# simple-loop-screwsfixed.net
KiCad netlist of a schematic drawn in EAGLE
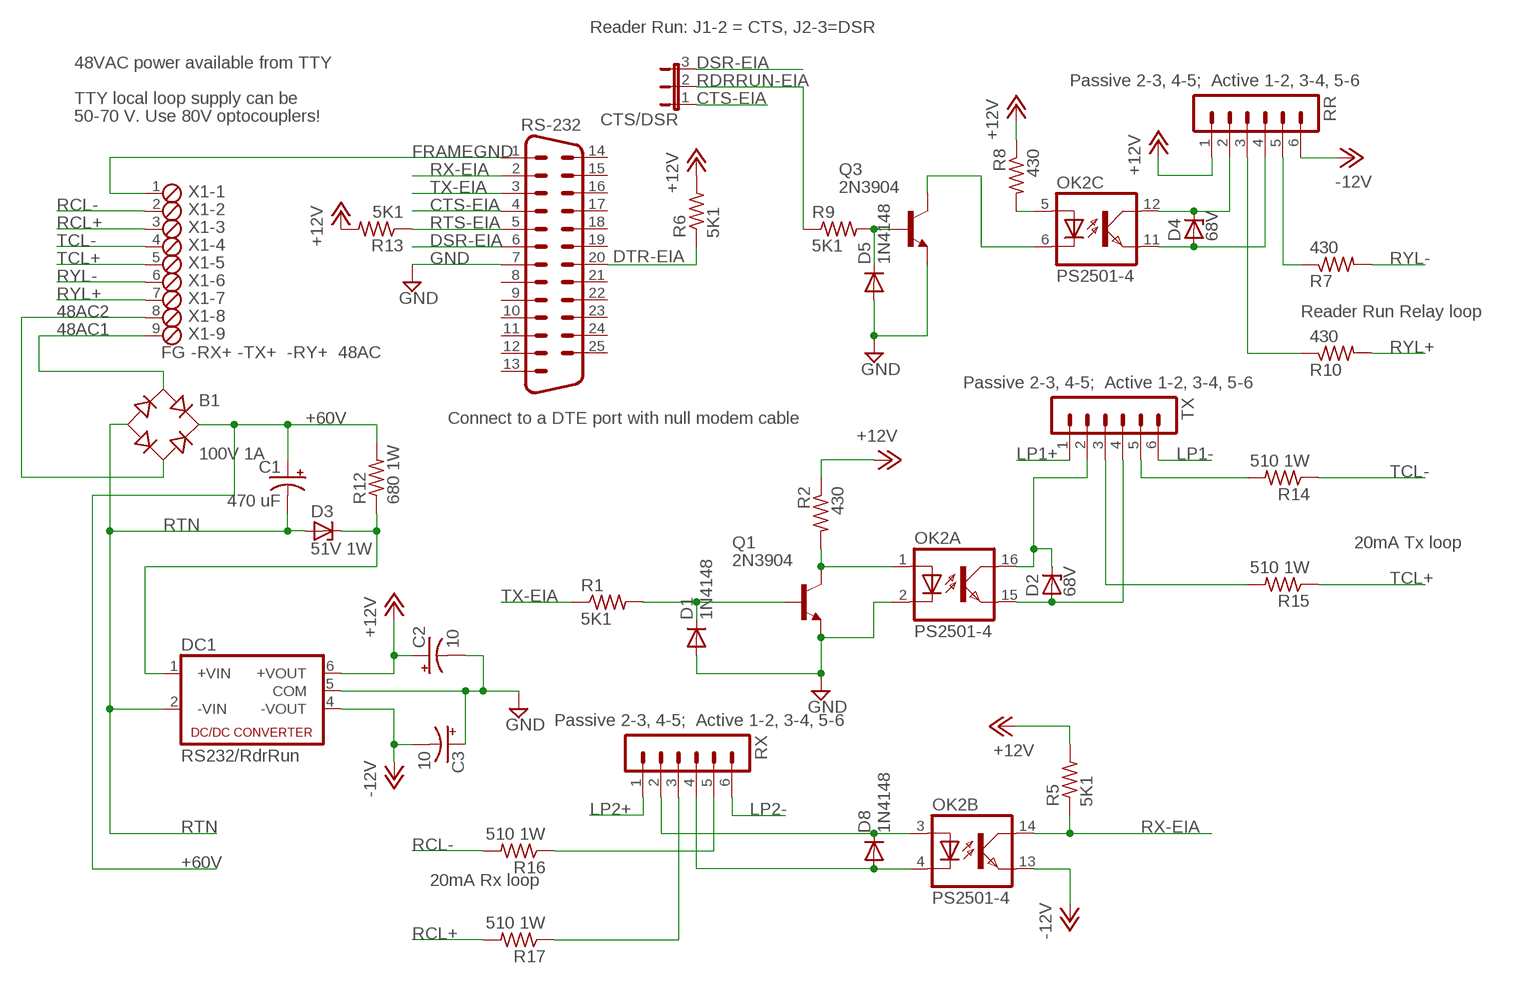
[diagram p0: schematic, sheet 1]
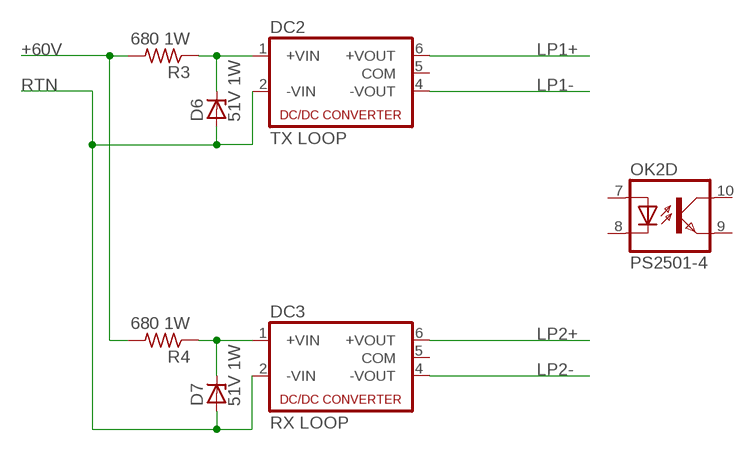
[diagram p1: schematic, sheet 2]

(export (version "E")
  (design (tool "Eeschema 10.0.6"))
  (components
    (comp (ref "B1")
      (value "100V 1A")
      (footprint "eagle-import:RB1A")
      (libsource (lib "eagle-import") (part "RB1A"))
    )
    (comp (ref "C1")
      (value "470 uF")
      (footprint "eagle-import:E7,5-18")
      (libsource (lib "eagle-import") (part "CPOL-USE7.5-18"))
    )
    (comp (ref "C2")
      (value "10")
      (footprint "eagle-import:B45181A")
      (libsource (lib "eagle-import") (part "CPOL-USB45181A"))
    )
    (comp (ref "C3")
      (value "10")
      (footprint "eagle-import:B45181A")
      (libsource (lib "eagle-import") (part "CPOL-USB45181A"))
    )
    (comp (ref "CTS/DSR")
      (value "JP2E")
      (footprint "eagle-import:JP2")
      (libsource (lib "eagle-import") (part "JP2E"))
    )
    (comp (ref "D1")
      (value "1N4148")
      (footprint "eagle-import:DO35-10")
      (libsource (lib "eagle-import") (part "1N4148DO35-10"))
    )
    (comp (ref "D2")
      (value "68V")
      (footprint "eagle-import:DO41Z10")
      (libsource (lib "eagle-import") (part "ZENER-DIODEDO41Z10"))
    )
    (comp (ref "D3")
      (value "51V 1W")
      (footprint "eagle-import:DO41Z10")
      (libsource (lib "eagle-import") (part "ZENER-DIODEDO41Z10"))
    )
    (comp (ref "D4")
      (value "68V")
      (footprint "eagle-import:DO41Z10")
      (libsource (lib "eagle-import") (part "ZENER-DIODEDO41Z10"))
    )
    (comp (ref "D5")
      (value "1N4148")
      (footprint "eagle-import:DO35-10")
      (libsource (lib "eagle-import") (part "1N4148DO35-10"))
    )
    (comp (ref "D8")
      (value "1N4148")
      (footprint "eagle-import:DO35-10")
      (libsource (lib "eagle-import") (part "1N4148DO35-10"))
    )
    (comp (ref "DC1")
      (value "RS232/RdrRun")
      (footprint "eagle-import:NMA")
      (fields (field (name "MF") "C & D TECHNOLOGIES, INC") (field (name "MPN") "NMA0515SC"))
      (libsource (lib "eagle-import") (part "NMA"))
    )
    (comp (ref "OK2")
      (value "PS2501-4")
      (footprint "eagle-import:DIL16")
      (libsource (lib "eagle-import") (part "PC847"))
    )
    (comp (ref "Q1")
      (value "2N3904")
      (footprint "eagle-import:TO92")
      (libsource (lib "eagle-import") (part "2N3904"))
    )
    (comp (ref "Q3")
      (value "2N3904")
      (footprint "eagle-import:TO92")
      (libsource (lib "eagle-import") (part "2N3904"))
    )
    (comp (ref "R1")
      (value "5K1")
      (footprint "eagle-import:0207_10")
      (libsource (lib "eagle-import") (part "R-US_0207/10"))
    )
    (comp (ref "R2")
      (value "430")
      (footprint "eagle-import:0207_10")
      (libsource (lib "eagle-import") (part "R-US_0207/10"))
    )
    (comp (ref "R5")
      (value "5K1")
      (footprint "eagle-import:0207_10")
      (libsource (lib "eagle-import") (part "R-US_0207/10"))
    )
    (comp (ref "R6")
      (value "5K1")
      (footprint "eagle-import:0207_10")
      (libsource (lib "eagle-import") (part "R-US_0207/10"))
    )
    (comp (ref "R7")
      (value "430")
      (footprint "eagle-import:0207_10")
      (libsource (lib "eagle-import") (part "R-US_0207/10"))
    )
    (comp (ref "R8")
      (value "430")
      (footprint "eagle-import:0207_10")
      (libsource (lib "eagle-import") (part "R-US_0207/10"))
    )
    (comp (ref "R9")
      (value "5K1")
      (footprint "eagle-import:0207_10")
      (libsource (lib "eagle-import") (part "R-US_0207/10"))
    )
    (comp (ref "R10")
      (value "430")
      (footprint "eagle-import:0207_10")
      (libsource (lib "eagle-import") (part "R-US_0207/10"))
    )
    (comp (ref "R12")
      (value "680 1W")
      (footprint "eagle-import:P0817V")
      (libsource (lib "eagle-import") (part "R-US_0817/7V"))
    )
    (comp (ref "R13")
      (value "5K1")
      (footprint "eagle-import:0207_10")
      (libsource (lib "eagle-import") (part "R-US_0207/10"))
    )
    (comp (ref "R14")
      (value "510 1W")
      (footprint "eagle-import:P0817V")
      (libsource (lib "eagle-import") (part "R-US_0817/7V"))
    )
    (comp (ref "R15")
      (value "510 1W")
      (footprint "eagle-import:P0817V")
      (libsource (lib "eagle-import") (part "R-US_0817/7V"))
    )
    (comp (ref "R16")
      (value "510 1W")
      (footprint "eagle-import:P0817V")
      (libsource (lib "eagle-import") (part "R-US_0817/7V"))
    )
    (comp (ref "R17")
      (value "510 1W")
      (footprint "eagle-import:P0817V")
      (libsource (lib "eagle-import") (part "R-US_0817/7V"))
    )
    (comp (ref "RR")
      (value "MA06-1")
      (footprint "eagle-import:MA06-1")
      (libsource (lib "eagle-import") (part "MA06-1"))
    )
    (comp (ref "RS-232")
      (value "M25H")
      (footprint "eagle-import:M25H")
      (libsource (lib "eagle-import") (part "M25H"))
    )
    (comp (ref "RX")
      (value "MA06-1")
      (footprint "eagle-import:MA06-1")
      (libsource (lib "eagle-import") (part "MA06-1"))
    )
    (comp (ref "TX")
      (value "MA06-1")
      (footprint "eagle-import:MA06-1")
      (libsource (lib "eagle-import") (part "MA06-1"))
    )
    (comp (ref "X1")
      (value "FG -RX+ -TX+ -RY+ 48AC")
      (footprint "eagle-import:9POL254")
      (libsource (lib "eagle-import") (part "MPT9"))
    )
    (comp (ref "D6")
      (value "51V 1W")
      (footprint "eagle-import:DO41Z10")
      (libsource (lib "eagle-import") (part "ZENER-DIODEDO41Z10"))
    )
    (comp (ref "D7")
      (value "51V 1W")
      (footprint "eagle-import:DO41Z10")
      (libsource (lib "eagle-import") (part "ZENER-DIODEDO41Z10"))
    )
    (comp (ref "DC2")
      (value "TX LOOP")
      (footprint "eagle-import:NMA")
      (fields (field (name "MF") "C & D TECHNOLOGIES, INC") (field (name "MPN") "NMA0515SC"))
      (libsource (lib "eagle-import") (part "NMA"))
    )
    (comp (ref "DC3")
      (value "RX LOOP")
      (footprint "eagle-import:NMA")
      (fields (field (name "MF") "C & D TECHNOLOGIES, INC") (field (name "MPN") "NMA0515SC"))
      (libsource (lib "eagle-import") (part "NMA"))
    )
    (comp (ref "R3")
      (value "680 1W")
      (footprint "eagle-import:P0817V")
      (libsource (lib "eagle-import") (part "R-US_0817/7V"))
    )
    (comp (ref "R4")
      (value "680 1W")
      (footprint "eagle-import:P0817V")
      (libsource (lib "eagle-import") (part "R-US_0817/7V"))
    )
  )
  (nets
    (net (code "1") (name "+12V") (class "Default")
      (node (ref "C2") (pin "+") (pinfunction "+_+") (pintype "passive"))
      (node (ref "DC1") (pin "6") (pinfunction "+VOUT_6") (pintype "passive"))
      (node (ref "R13") (pin "2") (pinfunction "2_2") (pintype "passive"))
      (node (ref "R2") (pin "1") (pinfunction "1_1") (pintype "passive"))
      (node (ref "R5") (pin "2") (pinfunction "2_2") (pintype "passive"))
      (node (ref "R6") (pin "2") (pinfunction "2_2") (pintype "passive"))
      (node (ref "R8") (pin "1") (pinfunction "1_1") (pintype "passive"))
      (node (ref "RR") (pin "1") (pinfunction "1_1") (pintype "passive"))
    )
    (net (code "2") (name "+60V") (class "Default")
      (node (ref "B1") (pin "+") (pinfunction "+_+") (pintype "passive"))
      (node (ref "C1") (pin "+") (pinfunction "+_+") (pintype "passive"))
      (node (ref "R12") (pin "2") (pinfunction "2_2") (pintype "passive"))
      (node (ref "R3") (pin "2") (pinfunction "2_2") (pintype "passive"))
      (node (ref "R4") (pin "2") (pinfunction "2_2") (pintype "passive"))
    )
    (net (code "3") (name "-12V") (class "Default")
      (node (ref "C3") (pin "-") (pinfunction "-_-") (pintype "passive"))
      (node (ref "DC1") (pin "4") (pinfunction "-VOUT_4") (pintype "passive"))
      (node (ref "OK2") (pin "13") (pinfunction "EMIT_13") (pintype "passive"))
      (node (ref "RR") (pin "6") (pinfunction "6_6") (pintype "passive"))
    )
    (net (code "4") (name "48AC1") (class "Default")
      (node (ref "B1") (pin "AC1") (pinfunction "AC1_AC1") (pintype "passive"))
      (node (ref "X1") (pin "9") (pinfunction "1_9") (pintype "passive"))
    )
    (net (code "5") (name "48AC2") (class "Default")
      (node (ref "B1") (pin "AC2") (pinfunction "AC2_AC2") (pintype "passive"))
      (node (ref "X1") (pin "8") (pinfunction "1_8") (pintype "passive"))
    )
    (net (code "6") (name "CTS-EIA") (class "Default")
      (node (ref "CTS/DSR") (pin "1") (pinfunction "1_1") (pintype "passive"))
      (node (ref "RS-232") (pin "4") (pinfunction "4_4") (pintype "passive"))
    )
    (net (code "7") (name "DSR-EIA") (class "Default")
      (node (ref "CTS/DSR") (pin "3") (pinfunction "3_3") (pintype "passive"))
      (node (ref "RS-232") (pin "6") (pinfunction "6_6") (pintype "passive"))
    )
    (net (code "8") (name "DTR-EIA") (class "Default")
      (node (ref "R6") (pin "1") (pinfunction "1_1") (pintype "passive"))
      (node (ref "RS-232") (pin "20") (pinfunction "20_20") (pintype "passive"))
    )
    (net (code "9") (name "FRAMEGND") (class "Default")
      (node (ref "RS-232") (pin "1") (pinfunction "1_1") (pintype "passive"))
      (node (ref "X1") (pin "1") (pinfunction "1_1") (pintype "passive"))
    )
    (net (code "10") (name "GND") (class "Default")
      (node (ref "C2") (pin "-") (pinfunction "-_-") (pintype "passive"))
      (node (ref "C3") (pin "+") (pinfunction "+_+") (pintype "passive"))
      (node (ref "D1") (pin "A") (pinfunction "A_A") (pintype "passive"))
      (node (ref "D5") (pin "A") (pinfunction "A_A") (pintype "passive"))
      (node (ref "DC1") (pin "5") (pinfunction "COM_5") (pintype "passive"))
      (node (ref "OK2") (pin "2") (pinfunction "C_2") (pintype "passive"))
      (node (ref "Q1") (pin "3") (pinfunction "E_3") (pintype "passive"))
      (node (ref "Q3") (pin "3") (pinfunction "E_3") (pintype "passive"))
      (node (ref "RS-232") (pin "7") (pinfunction "7_7") (pintype "passive"))
    )
    (net (code "11") (name "LP1+") (class "Default")
      (node (ref "DC2") (pin "6") (pinfunction "+VOUT_6") (pintype "passive"))
      (node (ref "TX") (pin "1") (pinfunction "1_1") (pintype "passive"))
    )
    (net (code "12") (name "LP1-") (class "Default")
      (node (ref "DC2") (pin "4") (pinfunction "-VOUT_4") (pintype "passive"))
      (node (ref "TX") (pin "6") (pinfunction "6_6") (pintype "passive"))
    )
    (net (code "13") (name "LP2+") (class "Default")
      (node (ref "DC3") (pin "6") (pinfunction "+VOUT_6") (pintype "passive"))
      (node (ref "RX") (pin "1") (pinfunction "1_1") (pintype "passive"))
    )
    (net (code "14") (name "LP2-") (class "Default")
      (node (ref "DC3") (pin "4") (pinfunction "-VOUT_4") (pintype "passive"))
      (node (ref "RX") (pin "6") (pinfunction "6_6") (pintype "passive"))
    )
    (net (code "15") (name "Net-(DC1-+VIN)") (class "Default")
      (node (ref "D3") (pin "C") (pinfunction "C_C") (pintype "passive"))
      (node (ref "DC1") (pin "1") (pinfunction "+VIN_1") (pintype "passive"))
      (node (ref "R12") (pin "1") (pinfunction "1_1") (pintype "passive"))
    )
    (net (code "16") (name "Net-(DC2-+VIN)") (class "Default")
      (node (ref "D6") (pin "C") (pinfunction "C_C") (pintype "passive"))
      (node (ref "DC2") (pin "1") (pinfunction "+VIN_1") (pintype "passive"))
      (node (ref "R3") (pin "1") (pinfunction "1_1") (pintype "passive"))
    )
    (net (code "17") (name "Net-(DC3-+VIN)") (class "Default")
      (node (ref "D7") (pin "C") (pinfunction "C_C") (pintype "passive"))
      (node (ref "DC3") (pin "1") (pinfunction "+VIN_1") (pintype "passive"))
      (node (ref "R4") (pin "1") (pinfunction "1_1") (pintype "passive"))
    )
    (net (code "18") (name "Net-(OK2A-A)") (class "Default")
      (node (ref "OK2") (pin "1") (pinfunction "A_1") (pintype "passive"))
      (node (ref "Q1") (pin "1") (pinfunction "C_1") (pintype "passive"))
      (node (ref "R2") (pin "2") (pinfunction "2_2") (pintype "passive"))
    )
    (net (code "19") (name "Net-(OK2A-COL)") (class "Default")
      (node (ref "D2") (pin "C") (pinfunction "C_C") (pintype "passive"))
      (node (ref "OK2") (pin "16") (pinfunction "COL_16") (pintype "passive"))
      (node (ref "TX") (pin "2") (pinfunction "2_2") (pintype "passive"))
    )
    (net (code "20") (name "Net-(OK2A-EMIT)") (class "Default")
      (node (ref "D2") (pin "A") (pinfunction "A_A") (pintype "passive"))
      (node (ref "OK2") (pin "15") (pinfunction "EMIT_15") (pintype "passive"))
      (node (ref "TX") (pin "4") (pinfunction "4_4") (pintype "passive"))
    )
    (net (code "21") (name "Net-(OK2B-A)") (class "Default")
      (node (ref "D8") (pin "C") (pinfunction "C_C") (pintype "passive"))
      (node (ref "OK2") (pin "3") (pinfunction "A_3") (pintype "passive"))
      (node (ref "RX") (pin "2") (pinfunction "2_2") (pintype "passive"))
    )
    (net (code "22") (name "Net-(OK2B-C)") (class "Default")
      (node (ref "D8") (pin "A") (pinfunction "A_A") (pintype "passive"))
      (node (ref "OK2") (pin "4") (pinfunction "C_4") (pintype "passive"))
      (node (ref "RX") (pin "4") (pinfunction "4_4") (pintype "passive"))
    )
    (net (code "23") (name "Net-(OK2C-A)") (class "Default")
      (node (ref "OK2") (pin "5") (pinfunction "A_5") (pintype "passive"))
      (node (ref "R8") (pin "2") (pinfunction "2_2") (pintype "passive"))
    )
    (net (code "24") (name "Net-(OK2C-C)") (class "Default")
      (node (ref "OK2") (pin "6") (pinfunction "C_6") (pintype "passive"))
      (node (ref "Q3") (pin "1") (pinfunction "C_1") (pintype "passive"))
    )
    (net (code "25") (name "Net-(OK2C-COL)") (class "Default")
      (node (ref "D4") (pin "C") (pinfunction "C_C") (pintype "passive"))
      (node (ref "OK2") (pin "12") (pinfunction "COL_12") (pintype "passive"))
      (node (ref "RR") (pin "2") (pinfunction "2_2") (pintype "passive"))
    )
    (net (code "26") (name "Net-(OK2C-EMIT)") (class "Default")
      (node (ref "D4") (pin "A") (pinfunction "A_A") (pintype "passive"))
      (node (ref "OK2") (pin "11") (pinfunction "EMIT_11") (pintype "passive"))
      (node (ref "RR") (pin "4") (pinfunction "4_4") (pintype "passive"))
    )
    (net (code "27") (name "Net-(Q1-B)") (class "Default")
      (node (ref "D1") (pin "C") (pinfunction "C_C") (pintype "passive"))
      (node (ref "Q1") (pin "2") (pinfunction "B_2") (pintype "passive"))
      (node (ref "R1") (pin "2") (pinfunction "2_2") (pintype "passive"))
    )
    (net (code "28") (name "Net-(Q3-B)") (class "Default")
      (node (ref "D5") (pin "C") (pinfunction "C_C") (pintype "passive"))
      (node (ref "Q3") (pin "2") (pinfunction "B_2") (pintype "passive"))
      (node (ref "R9") (pin "2") (pinfunction "2_2") (pintype "passive"))
    )
    (net (code "29") (name "Net-(R7-Pad1)") (class "Default")
      (node (ref "R7") (pin "1") (pinfunction "1_1") (pintype "passive"))
      (node (ref "RR") (pin "5") (pinfunction "5_5") (pintype "passive"))
    )
    (net (code "30") (name "Net-(R10-Pad1)") (class "Default")
      (node (ref "R10") (pin "1") (pinfunction "1_1") (pintype "passive"))
      (node (ref "RR") (pin "3") (pinfunction "3_3") (pintype "passive"))
    )
    (net (code "31") (name "Net-(R14-Pad2)") (class "Default")
      (node (ref "R14") (pin "2") (pinfunction "2_2") (pintype "passive"))
      (node (ref "TX") (pin "5") (pinfunction "5_5") (pintype "passive"))
    )
    (net (code "32") (name "Net-(R15-Pad2)") (class "Default")
      (node (ref "R15") (pin "2") (pinfunction "2_2") (pintype "passive"))
      (node (ref "TX") (pin "3") (pinfunction "3_3") (pintype "passive"))
    )
    (net (code "33") (name "Net-(R16-Pad1)") (class "Default")
      (node (ref "R16") (pin "1") (pinfunction "1_1") (pintype "passive"))
      (node (ref "RX") (pin "5") (pinfunction "5_5") (pintype "passive"))
    )
    (net (code "34") (name "Net-(R17-Pad1)") (class "Default")
      (node (ref "R17") (pin "1") (pinfunction "1_1") (pintype "passive"))
      (node (ref "RX") (pin "3") (pinfunction "3_3") (pintype "passive"))
    )
    (net (code "35") (name "RCL+") (class "Default")
      (node (ref "R17") (pin "2") (pinfunction "2_2") (pintype "passive"))
      (node (ref "X1") (pin "3") (pinfunction "1_3") (pintype "passive"))
    )
    (net (code "36") (name "RCL-") (class "Default")
      (node (ref "R16") (pin "2") (pinfunction "2_2") (pintype "passive"))
      (node (ref "X1") (pin "2") (pinfunction "1_2") (pintype "passive"))
    )
    (net (code "37") (name "RDRRUN-EIA") (class "Default")
      (node (ref "CTS/DSR") (pin "2") (pinfunction "2_2") (pintype "passive"))
      (node (ref "R9") (pin "1") (pinfunction "1_1") (pintype "passive"))
    )
    (net (code "38") (name "RTN") (class "Default")
      (node (ref "B1") (pin "-") (pinfunction "-_-") (pintype "passive"))
      (node (ref "C1") (pin "-") (pinfunction "-_-") (pintype "passive"))
      (node (ref "D3") (pin "A") (pinfunction "A_A") (pintype "passive"))
      (node (ref "D6") (pin "A") (pinfunction "A_A") (pintype "passive"))
      (node (ref "D7") (pin "A") (pinfunction "A_A") (pintype "passive"))
      (node (ref "DC1") (pin "2") (pinfunction "-VIN_2") (pintype "passive"))
      (node (ref "DC2") (pin "2") (pinfunction "-VIN_2") (pintype "passive"))
      (node (ref "DC3") (pin "2") (pinfunction "-VIN_2") (pintype "passive"))
    )
    (net (code "39") (name "RTS-EIA") (class "Default")
      (node (ref "R13") (pin "1") (pinfunction "1_1") (pintype "passive"))
      (node (ref "RS-232") (pin "5") (pinfunction "5_5") (pintype "passive"))
    )
    (net (code "40") (name "RX-EIA") (class "Default")
      (node (ref "OK2") (pin "14") (pinfunction "COL_14") (pintype "passive"))
      (node (ref "R5") (pin "1") (pinfunction "1_1") (pintype "passive"))
      (node (ref "RS-232") (pin "2") (pinfunction "2_2") (pintype "passive"))
    )
    (net (code "41") (name "RYL+") (class "Default")
      (node (ref "R10") (pin "2") (pinfunction "2_2") (pintype "passive"))
      (node (ref "X1") (pin "7") (pinfunction "1_7") (pintype "passive"))
    )
    (net (code "42") (name "RYL-") (class "Default")
      (node (ref "R7") (pin "2") (pinfunction "2_2") (pintype "passive"))
      (node (ref "X1") (pin "6") (pinfunction "1_6") (pintype "passive"))
    )
    (net (code "43") (name "TCL+") (class "Default")
      (node (ref "R15") (pin "1") (pinfunction "1_1") (pintype "passive"))
      (node (ref "X1") (pin "5") (pinfunction "1_5") (pintype "passive"))
    )
    (net (code "44") (name "TCL-") (class "Default")
      (node (ref "R14") (pin "1") (pinfunction "1_1") (pintype "passive"))
      (node (ref "X1") (pin "4") (pinfunction "1_4") (pintype "passive"))
    )
    (net (code "45") (name "TX-EIA") (class "Default")
      (node (ref "R1") (pin "1") (pinfunction "1_1") (pintype "passive"))
      (node (ref "RS-232") (pin "3") (pinfunction "3_3") (pintype "passive"))
    )
    (net (code "46") (name "unconnected-(DC2-COM-Pad5)") (class "Default")
      (node (ref "DC2") (pin "5") (pinfunction "COM_5") (pintype "passive"))
    )
    (net (code "47") (name "unconnected-(DC3-COM-Pad5)") (class "Default")
      (node (ref "DC3") (pin "5") (pinfunction "COM_5") (pintype "passive"))
    )
    (net (code "48") (name "unconnected-(OK2D-A-Pad7)") (class "Default")
      (node (ref "OK2") (pin "7") (pinfunction "A_7") (pintype "passive"))
    )
    (net (code "49") (name "unconnected-(OK2D-C-Pad8)") (class "Default")
      (node (ref "OK2") (pin "8") (pinfunction "C_8") (pintype "passive"))
    )
    (net (code "50") (name "unconnected-(OK2D-COL-Pad10)") (class "Default")
      (node (ref "OK2") (pin "10") (pinfunction "COL_10") (pintype "passive"))
    )
    (net (code "51") (name "unconnected-(OK2D-EMIT-Pad9)") (class "Default")
      (node (ref "OK2") (pin "9") (pinfunction "EMIT_9") (pintype "passive"))
    )
    (net (code "52") (name "unconnected-(RS-232-Pad8)") (class "Default")
      (node (ref "RS-232") (pin "8") (pinfunction "8_8") (pintype "passive"))
    )
    (net (code "53") (name "unconnected-(RS-232-Pad9)") (class "Default")
      (node (ref "RS-232") (pin "9") (pinfunction "9_9") (pintype "passive"))
    )
    (net (code "54") (name "unconnected-(RS-232-Pad10)") (class "Default")
      (node (ref "RS-232") (pin "10") (pinfunction "10_10") (pintype "passive"))
    )
    (net (code "55") (name "unconnected-(RS-232-Pad11)") (class "Default")
      (node (ref "RS-232") (pin "11") (pinfunction "11_11") (pintype "passive"))
    )
    (net (code "56") (name "unconnected-(RS-232-Pad12)") (class "Default")
      (node (ref "RS-232") (pin "12") (pinfunction "12_12") (pintype "passive"))
    )
    (net (code "57") (name "unconnected-(RS-232-Pad13)") (class "Default")
      (node (ref "RS-232") (pin "13") (pinfunction "13_13") (pintype "passive"))
    )
    (net (code "58") (name "unconnected-(RS-232-Pad14)") (class "Default")
      (node (ref "RS-232") (pin "14") (pinfunction "14_14") (pintype "passive"))
    )
    (net (code "59") (name "unconnected-(RS-232-Pad15)") (class "Default")
      (node (ref "RS-232") (pin "15") (pinfunction "15_15") (pintype "passive"))
    )
    (net (code "60") (name "unconnected-(RS-232-Pad16)") (class "Default")
      (node (ref "RS-232") (pin "16") (pinfunction "16_16") (pintype "passive"))
    )
    (net (code "61") (name "unconnected-(RS-232-Pad17)") (class "Default")
      (node (ref "RS-232") (pin "17") (pinfunction "17_17") (pintype "passive"))
    )
    (net (code "62") (name "unconnected-(RS-232-Pad18)") (class "Default")
      (node (ref "RS-232") (pin "18") (pinfunction "18_18") (pintype "passive"))
    )
    (net (code "63") (name "unconnected-(RS-232-Pad19)") (class "Default")
      (node (ref "RS-232") (pin "19") (pinfunction "19_19") (pintype "passive"))
    )
    (net (code "64") (name "unconnected-(RS-232-Pad21)") (class "Default")
      (node (ref "RS-232") (pin "21") (pinfunction "21_21") (pintype "passive"))
    )
    (net (code "65") (name "unconnected-(RS-232-Pad22)") (class "Default")
      (node (ref "RS-232") (pin "22") (pinfunction "22_22") (pintype "passive"))
    )
    (net (code "66") (name "unconnected-(RS-232-Pad23)") (class "Default")
      (node (ref "RS-232") (pin "23") (pinfunction "23_23") (pintype "passive"))
    )
    (net (code "67") (name "unconnected-(RS-232-Pad24)") (class "Default")
      (node (ref "RS-232") (pin "24") (pinfunction "24_24") (pintype "passive"))
    )
    (net (code "68") (name "unconnected-(RS-232-Pad25)") (class "Default")
      (node (ref "RS-232") (pin "25") (pinfunction "25_25") (pintype "passive"))
    )
  )
)
